# Solar_Charge_Controller.net
KiCad netlist of a schematic drawn in EAGLE
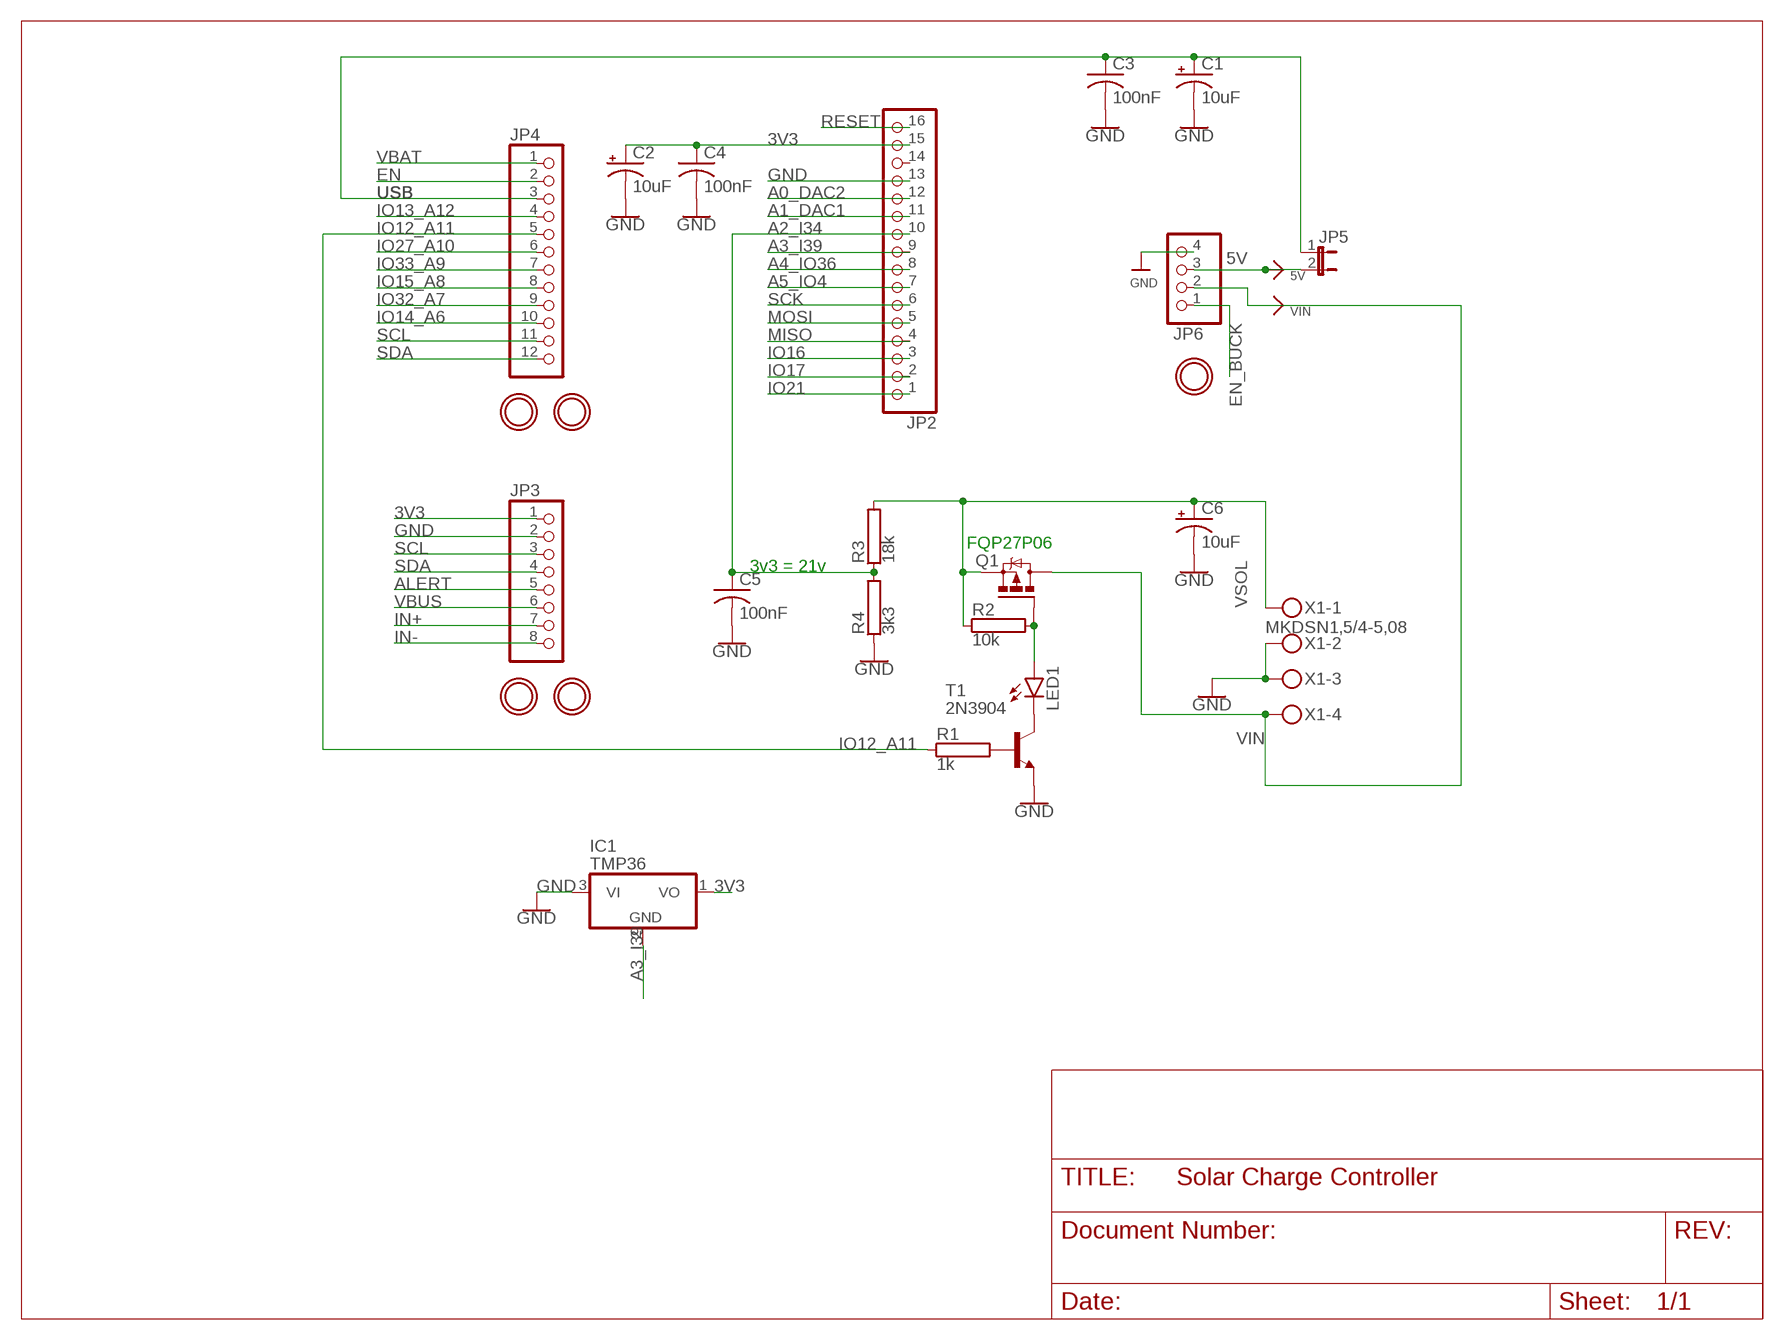
[diagram p0: schematic, sheet 1]

(export (version "E")
  (design (tool "Eeschema 10.0.6"))
  (components
    (comp (ref "C1")
      (value "10uF")
      (footprint "eagle-import:E2,5-5")
      (libsource (lib "eagle-import") (part "CPOL-USE2.5-5"))
    )
    (comp (ref "C2")
      (value "10uF")
      (footprint "eagle-import:E2,5-5")
      (libsource (lib "eagle-import") (part "CPOL-USE2.5-5"))
    )
    (comp (ref "C3")
      (value "100nF")
      (footprint "eagle-import:C025-024X044")
      (libsource (lib "eagle-import") (part "C-US025-024X044"))
    )
    (comp (ref "C4")
      (value "100nF")
      (footprint "eagle-import:C025-024X044")
      (libsource (lib "eagle-import") (part "C-US025-024X044"))
    )
    (comp (ref "C5")
      (value "100nF")
      (footprint "eagle-import:C025-024X044")
      (libsource (lib "eagle-import") (part "C-US025-024X044"))
    )
    (comp (ref "C6")
      (value "10uF")
      (footprint "eagle-import:E2,5-5")
      (libsource (lib "eagle-import") (part "CPOL-USE2.5-5"))
    )
    (comp (ref "IC1")
      (value "TMP36")
      (footprint "eagle-import:TO92")
      (libsource (lib "eagle-import") (part "78ZL05"))
    )
    (comp (ref "JP2")
      (value "HEADER-1X16_MIN")
      (footprint "eagle-import:1X16_ROUND_MIN")
      (libsource (lib "eagle-import") (part "HEADER-1X16_MIN"))
    )
    (comp (ref "JP3")
      (value "HEADER-1X870MIL")
      (footprint "eagle-import:1X08_ROUND_70")
      (libsource (lib "eagle-import") (part "HEADER-1X870MIL"))
    )
    (comp (ref "JP4")
      (value "HEADER-1X12_MIN")
      (footprint "eagle-import:1X12_ROUND_MIN")
      (libsource (lib "eagle-import") (part "HEADER-1X12_MIN"))
    )
    (comp (ref "JP5")
      (value "JP1E")
      (footprint "eagle-import:JP1")
      (libsource (lib "eagle-import") (part "JP1E"))
    )
    (comp (ref "JP6")
      (value "HEADER-1X4ROUND")
      (footprint "eagle-import:1X04_ROUND")
      (libsource (lib "eagle-import") (part "HEADER-1X4ROUND"))
    )
    (comp (ref "LED1")
      (value "LED3MM")
      (footprint "eagle-import:LED3MM")
      (libsource (lib "eagle-import") (part "LED3MM"))
    )
    (comp (ref "Q1")
      (value "FQP27P06")
      (footprint "eagle-import:TO220BV")
      (libsource (lib "eagle-import") (part "IRF9530"))
    )
    (comp (ref "R1")
      (value "1k")
      (footprint "eagle-import:RS1_4")
      (fields (field (name "MF") "OHMITE") (field (name "MPN") "RRS1K0"))
      (libsource (lib "eagle-import") (part "RRS1/4"))
    )
    (comp (ref "R2")
      (value "10k")
      (footprint "eagle-import:RS1_4")
      (fields (field (name "MF") "OHMITE") (field (name "MPN") "RRS1K0"))
      (libsource (lib "eagle-import") (part "RRS1/4"))
    )
    (comp (ref "R3")
      (value "18k")
      (footprint "eagle-import:RS1_4")
      (fields (field (name "MF") "OHMITE") (field (name "MPN") "RRS1K0"))
      (libsource (lib "eagle-import") (part "RRS1/4"))
    )
    (comp (ref "R4")
      (value "3k3")
      (footprint "eagle-import:RS1_4")
      (fields (field (name "MF") "OHMITE") (field (name "MPN") "RRS1K0"))
      (libsource (lib "eagle-import") (part "RRS1/4"))
    )
    (comp (ref "T1")
      (value "2N3904")
      (footprint "eagle-import:TO92")
      (libsource (lib "eagle-import") (part "2N3904"))
    )
    (comp (ref "U$2")
      (value "MOUNTINGHOLE2.5")
      (footprint "eagle-import:MOUNTINGHOLE_2.5_PLATED")
      (libsource (lib "eagle-import") (part "MOUNTINGHOLE2.5"))
    )
    (comp (ref "U$3")
      (value "MOUNTINGHOLE2.5")
      (footprint "eagle-import:MOUNTINGHOLE_2.5_PLATED")
      (libsource (lib "eagle-import") (part "MOUNTINGHOLE2.5"))
    )
    (comp (ref "U$4")
      (value "MOUNTINGHOLE2.5")
      (footprint "eagle-import:MOUNTINGHOLE_2.5_PLATED")
      (libsource (lib "eagle-import") (part "MOUNTINGHOLE2.5"))
    )
    (comp (ref "U$5")
      (value "MOUNTINGHOLE2.5")
      (footprint "eagle-import:MOUNTINGHOLE_2.5_PLATED")
      (libsource (lib "eagle-import") (part "MOUNTINGHOLE2.5"))
    )
    (comp (ref "U$12")
      (value "MOUNTINGHOLE2.5")
      (footprint "eagle-import:MOUNTINGHOLE_2.5_PLATED")
      (libsource (lib "eagle-import") (part "MOUNTINGHOLE2.5"))
    )
    (comp (ref "X1")
      (value "MKDSN1,5/4-5,08")
      (footprint "eagle-import:MKDSN1,5_4-5,08")
      (libsource (lib "eagle-import") (part "MKDSN1,5/4-5,08"))
    )
  )
  (nets
    (net (code "1") (name "/3V3") (class "Default")
      (node (ref "C2") (pin "+") (pinfunction "+_+") (pintype "passive"))
      (node (ref "C4") (pin "1") (pinfunction "1_1") (pintype "passive"))
      (node (ref "IC1") (pin "1") (pinfunction "VO_1") (pintype "passive"))
      (node (ref "JP2") (pin "15") (pinfunction "15_15") (pintype "passive"))
      (node (ref "JP3") (pin "1") (pinfunction "1_1") (pintype "passive"))
    )
    (net (code "2") (name "/A0_DAC2") (class "Default")
      (node (ref "JP2") (pin "12") (pinfunction "12_12") (pintype "passive"))
    )
    (net (code "3") (name "/A1_DAC1") (class "Default")
      (node (ref "JP2") (pin "11") (pinfunction "11_11") (pintype "passive"))
    )
    (net (code "4") (name "/A2_I34") (class "Default")
      (node (ref "C5") (pin "1") (pinfunction "1_1") (pintype "passive"))
      (node (ref "JP2") (pin "10") (pinfunction "10_10") (pintype "passive"))
      (node (ref "R3") (pin "1") (pinfunction "1_1") (pintype "passive"))
      (node (ref "R4") (pin "2") (pinfunction "2_2") (pintype "passive"))
    )
    (net (code "5") (name "/A3_I39") (class "Default")
      (node (ref "IC1") (pin "2") (pinfunction "GND_2") (pintype "passive"))
      (node (ref "JP2") (pin "9") (pinfunction "9_9") (pintype "passive"))
    )
    (net (code "6") (name "/A4_IO36") (class "Default")
      (node (ref "JP2") (pin "8") (pinfunction "8_8") (pintype "passive"))
    )
    (net (code "7") (name "/A5_IO4") (class "Default")
      (node (ref "JP2") (pin "7") (pinfunction "7_7") (pintype "passive"))
    )
    (net (code "8") (name "/ALERT") (class "Default")
      (node (ref "JP3") (pin "5") (pinfunction "5_5") (pintype "passive"))
    )
    (net (code "9") (name "/EN") (class "Default")
      (node (ref "JP4") (pin "2") (pinfunction "2_2") (pintype "passive"))
    )
    (net (code "10") (name "/EN_BUCK") (class "Default")
      (node (ref "JP6") (pin "1") (pinfunction "1_1") (pintype "passive"))
    )
    (net (code "11") (name "/IN+") (class "Default")
      (node (ref "JP3") (pin "7") (pinfunction "7_7") (pintype "passive"))
    )
    (net (code "12") (name "/IN-") (class "Default")
      (node (ref "JP3") (pin "8") (pinfunction "8_8") (pintype "passive"))
    )
    (net (code "13") (name "/IO12_A11") (class "Default")
      (node (ref "JP4") (pin "5") (pinfunction "5_5") (pintype "passive"))
      (node (ref "R1") (pin "1") (pinfunction "1_1") (pintype "passive"))
    )
    (net (code "14") (name "/IO13_A12") (class "Default")
      (node (ref "JP4") (pin "4") (pinfunction "4_4") (pintype "passive"))
    )
    (net (code "15") (name "/IO14_A6") (class "Default")
      (node (ref "JP4") (pin "10") (pinfunction "10_10") (pintype "passive"))
    )
    (net (code "16") (name "/IO15_A8") (class "Default")
      (node (ref "JP4") (pin "8") (pinfunction "8_8") (pintype "passive"))
    )
    (net (code "17") (name "/IO16") (class "Default")
      (node (ref "JP2") (pin "3") (pinfunction "3_3") (pintype "passive"))
    )
    (net (code "18") (name "/IO17") (class "Default")
      (node (ref "JP2") (pin "2") (pinfunction "2_2") (pintype "passive"))
    )
    (net (code "19") (name "/IO21") (class "Default")
      (node (ref "JP2") (pin "1") (pinfunction "1_1") (pintype "passive"))
    )
    (net (code "20") (name "/IO27_A10") (class "Default")
      (node (ref "JP4") (pin "6") (pinfunction "6_6") (pintype "passive"))
    )
    (net (code "21") (name "/IO32_A7") (class "Default")
      (node (ref "JP4") (pin "9") (pinfunction "9_9") (pintype "passive"))
    )
    (net (code "22") (name "/IO33_A9") (class "Default")
      (node (ref "JP4") (pin "7") (pinfunction "7_7") (pintype "passive"))
    )
    (net (code "23") (name "/MISO") (class "Default")
      (node (ref "JP2") (pin "4") (pinfunction "4_4") (pintype "passive"))
    )
    (net (code "24") (name "/MOSI") (class "Default")
      (node (ref "JP2") (pin "5") (pinfunction "5_5") (pintype "passive"))
    )
    (net (code "25") (name "/RESET") (class "Default")
      (node (ref "JP2") (pin "16") (pinfunction "16_16") (pintype "passive"))
    )
    (net (code "26") (name "/SCK") (class "Default")
      (node (ref "JP2") (pin "6") (pinfunction "6_6") (pintype "passive"))
    )
    (net (code "27") (name "/SCL") (class "Default")
      (node (ref "JP3") (pin "3") (pinfunction "3_3") (pintype "passive"))
      (node (ref "JP4") (pin "11") (pinfunction "11_11") (pintype "passive"))
    )
    (net (code "28") (name "/SDA") (class "Default")
      (node (ref "JP3") (pin "4") (pinfunction "4_4") (pintype "passive"))
      (node (ref "JP4") (pin "12") (pinfunction "12_12") (pintype "passive"))
    )
    (net (code "29") (name "/USB") (class "Default")
      (node (ref "C1") (pin "+") (pinfunction "+_+") (pintype "passive"))
      (node (ref "C3") (pin "1") (pinfunction "1_1") (pintype "passive"))
      (node (ref "JP4") (pin "3") (pinfunction "3_3") (pintype "passive"))
      (node (ref "JP5") (pin "1") (pinfunction "1_1") (pintype "passive"))
    )
    (net (code "30") (name "/VBAT") (class "Default")
      (node (ref "JP4") (pin "1") (pinfunction "1_1") (pintype "passive"))
    )
    (net (code "31") (name "/VBUS") (class "Default")
      (node (ref "JP3") (pin "6") (pinfunction "6_6") (pintype "passive"))
    )
    (net (code "32") (name "/VSOL") (class "Default")
      (node (ref "C6") (pin "+") (pinfunction "+_+") (pintype "passive"))
      (node (ref "Q1") (pin "S") (pinfunction "S_S") (pintype "passive"))
      (node (ref "R2") (pin "1") (pinfunction "1_1") (pintype "passive"))
      (node (ref "R3") (pin "2") (pinfunction "2_2") (pintype "passive"))
      (node (ref "X1") (pin "1") (pinfunction "KL_1") (pintype "passive"))
    )
    (net (code "33") (name "5V") (class "Default")
      (node (ref "JP5") (pin "2") (pinfunction "2_2") (pintype "passive"))
      (node (ref "JP6") (pin "3") (pinfunction "3_3") (pintype "passive"))
    )
    (net (code "34") (name "GND") (class "Default")
      (node (ref "C1") (pin "-") (pinfunction "-_-") (pintype "passive"))
      (node (ref "C2") (pin "-") (pinfunction "-_-") (pintype "passive"))
      (node (ref "C3") (pin "2") (pinfunction "2_2") (pintype "passive"))
      (node (ref "C4") (pin "2") (pinfunction "2_2") (pintype "passive"))
      (node (ref "C5") (pin "2") (pinfunction "2_2") (pintype "passive"))
      (node (ref "C6") (pin "-") (pinfunction "-_-") (pintype "passive"))
      (node (ref "IC1") (pin "3") (pinfunction "VI_3") (pintype "input"))
      (node (ref "JP2") (pin "13") (pinfunction "13_13") (pintype "passive"))
      (node (ref "JP3") (pin "2") (pinfunction "2_2") (pintype "passive"))
      (node (ref "JP6") (pin "4") (pinfunction "4_4") (pintype "passive"))
      (node (ref "R4") (pin "1") (pinfunction "1_1") (pintype "passive"))
      (node (ref "T1") (pin "3") (pinfunction "E_3") (pintype "passive"))
      (node (ref "X1") (pin "2") (pinfunction "KL_2") (pintype "passive"))
      (node (ref "X1") (pin "3") (pinfunction "KL_3") (pintype "passive"))
    )
    (net (code "35") (name "Net-(LED1-C)") (class "Default")
      (node (ref "LED1") (pin "K") (pinfunction "C_K") (pintype "passive"))
      (node (ref "T1") (pin "1") (pinfunction "C_1") (pintype "passive"))
    )
    (net (code "36") (name "Net-(LED1-PadA)") (class "Default")
      (node (ref "LED1") (pin "A") (pinfunction "A_A") (pintype "passive"))
      (node (ref "Q1") (pin "G") (pinfunction "G_G") (pintype "passive"))
      (node (ref "R2") (pin "2") (pinfunction "2_2") (pintype "passive"))
    )
    (net (code "37") (name "Net-(T1-B)") (class "Default")
      (node (ref "R1") (pin "2") (pinfunction "2_2") (pintype "passive"))
      (node (ref "T1") (pin "2") (pinfunction "B_2") (pintype "passive"))
    )
    (net (code "38") (name "VIN") (class "Default")
      (node (ref "JP6") (pin "2") (pinfunction "2_2") (pintype "passive"))
      (node (ref "Q1") (pin "D") (pinfunction "D_D") (pintype "passive"))
      (node (ref "X1") (pin "4") (pinfunction "KL_4") (pintype "passive"))
    )
    (net (code "39") (name "unconnected-(JP2-Pad14)") (class "Default")
      (node (ref "JP2") (pin "14") (pinfunction "14_14") (pintype "passive"))
    )
  )
)
